# BeautifulRobot.net
KiCad netlist of a schematic drawn in EAGLE
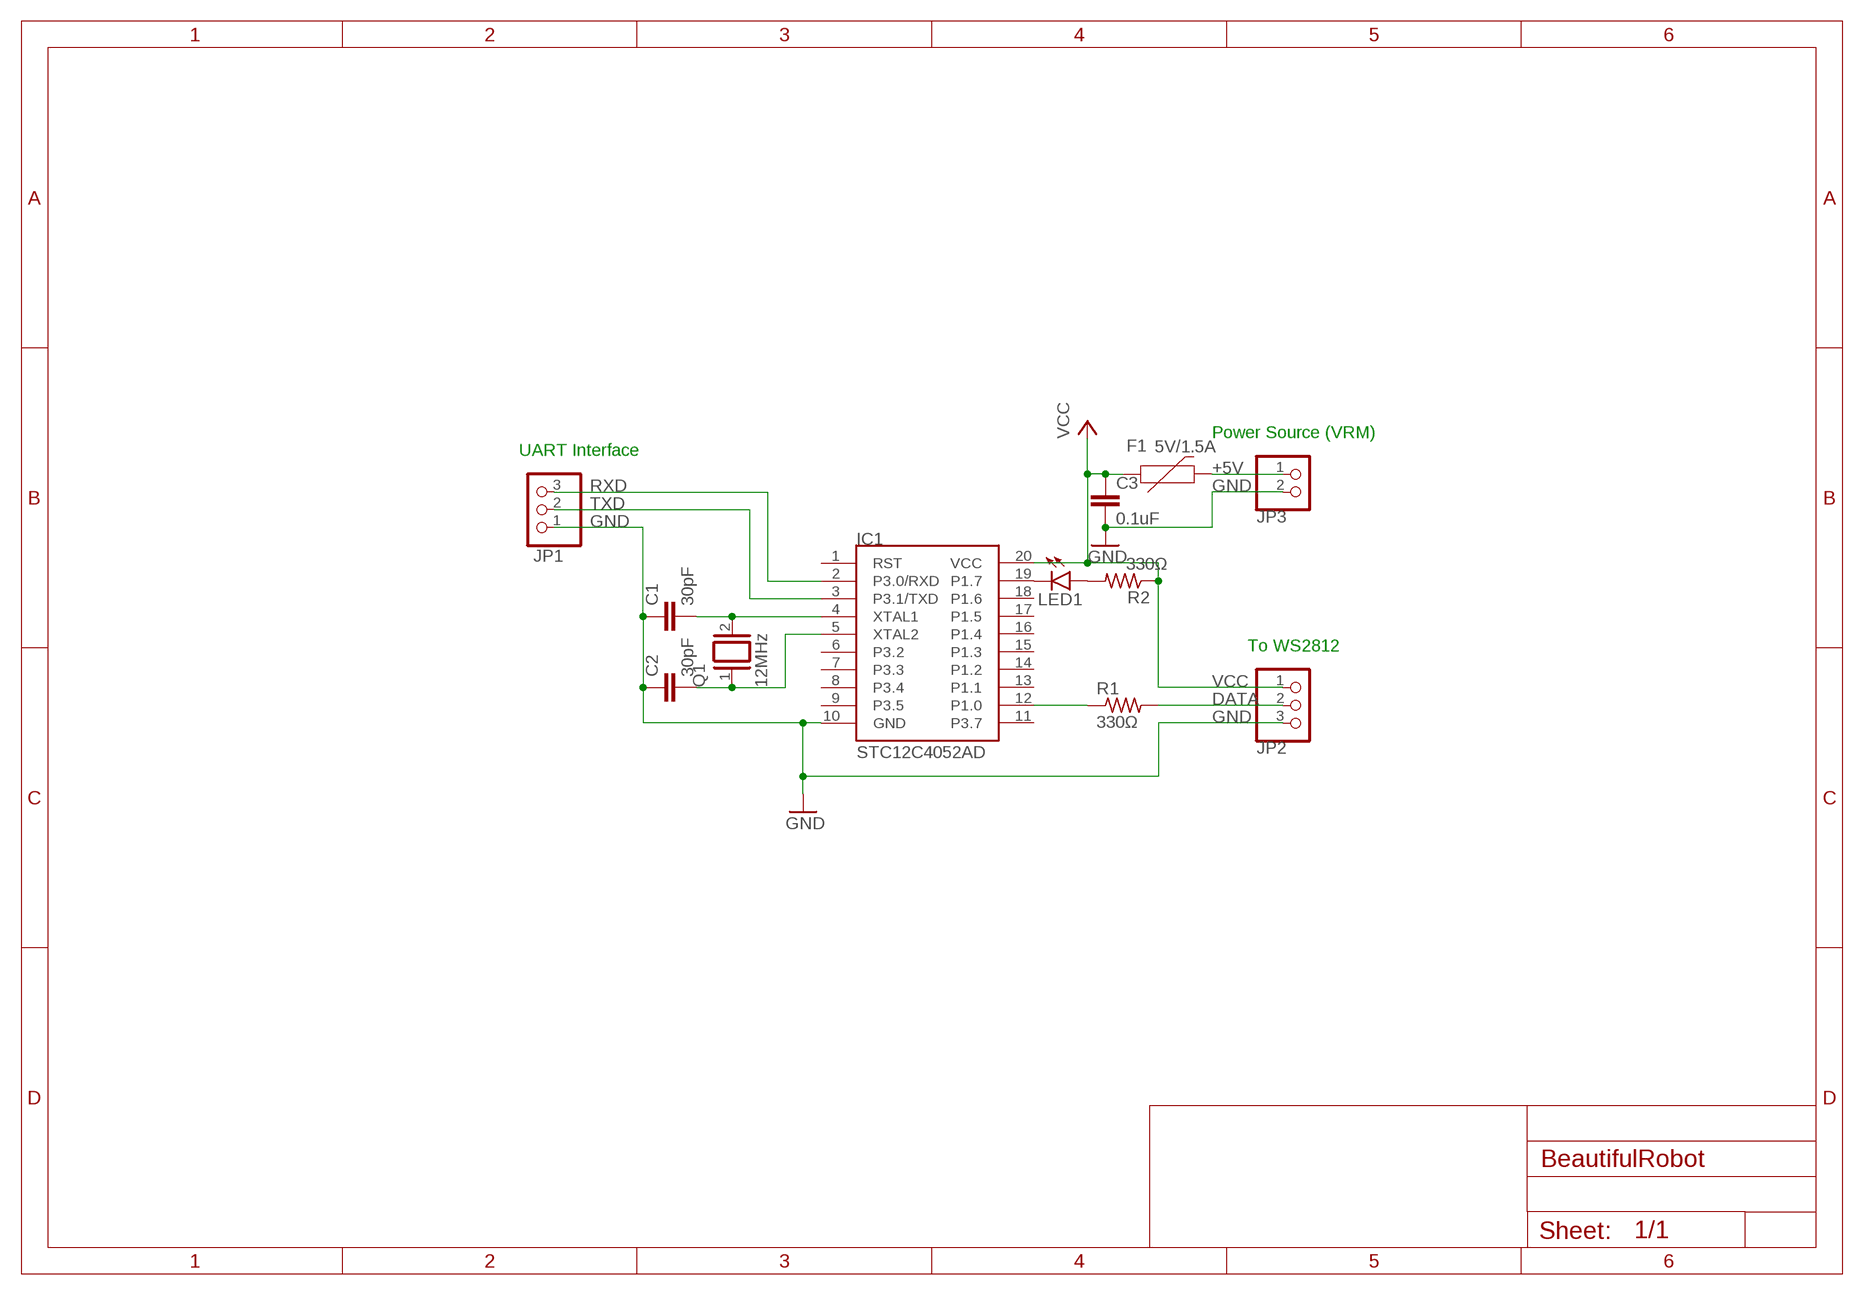
[diagram p0: schematic, sheet 1]

(export (version "E")
  (design (tool "Eeschema 10.0.6"))
  (components
    (comp (ref "C1")
      (value "30pF")
      (footprint "eagle-import:C025-025X050")
      (libsource (lib "eagle-import") (part "C-EU025-025X050"))
    )
    (comp (ref "C2")
      (value "30pF")
      (footprint "eagle-import:C025-025X050")
      (libsource (lib "eagle-import") (part "C-EU025-025X050"))
    )
    (comp (ref "C3")
      (value "0.1uF")
      (footprint "eagle-import:C025-025X050")
      (libsource (lib "eagle-import") (part "C-EU025-025X050"))
    )
    (comp (ref "F1")
      (value "5V/1.5A")
      (footprint "eagle-import:PTH")
      (libsource (lib "eagle-import") (part "PPTC_PTH"))
    )
    (comp (ref "IC1")
      (value "STC12C4052AD")
      (footprint "eagle-import:DIP762W40P254L2606H508Q20B")
      (libsource (lib "eagle-import") (part "STC12C4052AD"))
    )
    (comp (ref "JP1")
      (value "PINHD-1X3")
      (footprint "eagle-import:1X03")
      (libsource (lib "eagle-import") (part "PINHD-1X3"))
    )
    (comp (ref "JP2")
      (value "PINHD-1X3")
      (footprint "eagle-import:1X03")
      (libsource (lib "eagle-import") (part "PINHD-1X3"))
    )
    (comp (ref "JP3")
      (value "PINHD-1X2")
      (footprint "eagle-import:1X02")
      (libsource (lib "eagle-import") (part "PINHD-1X2"))
    )
    (comp (ref "LED1")
      (value "LED5MM")
      (footprint "eagle-import:LED5MM")
      (libsource (lib "eagle-import") (part "LED5MM"))
    )
    (comp (ref "Q1")
      (value "12MHz")
      (footprint "eagle-import:QS")
      (libsource (lib "eagle-import") (part "XTAL/S"))
    )
    (comp (ref "R1")
      (value "330Ω")
      (footprint "eagle-import:0204_7")
      (libsource (lib "eagle-import") (part "R-US_0204/7"))
    )
    (comp (ref "R2")
      (value "330Ω")
      (footprint "eagle-import:0204_7")
      (libsource (lib "eagle-import") (part "R-US_0204/7"))
    )
  )
  (nets
    (net (code "1") (name "/+5V") (class "Default")
      (node (ref "F1") (pin "P$2") (pinfunction "2_P$2") (pintype "bidirectional"))
      (node (ref "JP3") (pin "1") (pinfunction "1_1") (pintype "passive"))
    )
    (net (code "2") (name "/DATA") (class "Default")
      (node (ref "JP2") (pin "2") (pinfunction "2_2") (pintype "passive"))
      (node (ref "R1") (pin "2") (pinfunction "2_2") (pintype "passive"))
    )
    (net (code "3") (name "/RXD") (class "Default")
      (node (ref "IC1") (pin "2") (pinfunction "P3.0/RXD_2") (pintype "bidirectional"))
      (node (ref "JP1") (pin "3") (pinfunction "3_3") (pintype "passive"))
    )
    (net (code "4") (name "/TXD") (class "Default")
      (node (ref "IC1") (pin "3") (pinfunction "P3.1/TXD_3") (pintype "bidirectional"))
      (node (ref "JP1") (pin "2") (pinfunction "2_2") (pintype "passive"))
    )
    (net (code "5") (name "GND") (class "Default")
      (node (ref "C1") (pin "1") (pinfunction "1_1") (pintype "passive"))
      (node (ref "C2") (pin "1") (pinfunction "1_1") (pintype "passive"))
      (node (ref "C3") (pin "2") (pinfunction "2_2") (pintype "passive"))
      (node (ref "IC1") (pin "10") (pinfunction "GND_10") (pintype "power_in"))
      (node (ref "JP1") (pin "1") (pinfunction "1_1") (pintype "passive"))
      (node (ref "JP2") (pin "3") (pinfunction "3_3") (pintype "passive"))
      (node (ref "JP3") (pin "2") (pinfunction "2_2") (pintype "passive"))
    )
    (net (code "6") (name "Net-(IC1-P1.0)") (class "Default")
      (node (ref "IC1") (pin "12") (pinfunction "P1.0_12") (pintype "bidirectional"))
      (node (ref "R1") (pin "1") (pinfunction "1_1") (pintype "passive"))
    )
    (net (code "7") (name "Net-(IC1-P1.7)") (class "Default")
      (node (ref "IC1") (pin "19") (pinfunction "P1.7_19") (pintype "bidirectional"))
      (node (ref "LED1") (pin "K") (pinfunction "C_K") (pintype "passive"))
    )
    (net (code "8") (name "Net-(IC1-XTAL1)") (class "Default")
      (node (ref "C1") (pin "2") (pinfunction "2_2") (pintype "passive"))
      (node (ref "IC1") (pin "4") (pinfunction "XTAL1_4") (pintype "bidirectional"))
      (node (ref "Q1") (pin "2") (pinfunction "2_2") (pintype "passive"))
    )
    (net (code "9") (name "Net-(IC1-XTAL2)") (class "Default")
      (node (ref "C2") (pin "2") (pinfunction "2_2") (pintype "passive"))
      (node (ref "IC1") (pin "5") (pinfunction "XTAL2_5") (pintype "bidirectional"))
      (node (ref "Q1") (pin "1") (pinfunction "1_1") (pintype "passive"))
    )
    (net (code "10") (name "Net-(LED1-PadA)") (class "Default")
      (node (ref "LED1") (pin "A") (pinfunction "A_A") (pintype "passive"))
      (node (ref "R2") (pin "2") (pinfunction "2_2") (pintype "passive"))
    )
    (net (code "11") (name "VCC") (class "Default")
      (node (ref "C3") (pin "1") (pinfunction "1_1") (pintype "passive"))
      (node (ref "F1") (pin "P$1") (pinfunction "1_P$1") (pintype "bidirectional"))
      (node (ref "IC1") (pin "20") (pinfunction "VCC_20") (pintype "power_in"))
      (node (ref "JP2") (pin "1") (pinfunction "1_1") (pintype "passive"))
      (node (ref "R2") (pin "1") (pinfunction "1_1") (pintype "passive"))
    )
    (net (code "12") (name "unconnected-(IC1-P1.1-Pad13)") (class "Default")
      (node (ref "IC1") (pin "13") (pinfunction "P1.1_13") (pintype "bidirectional"))
    )
    (net (code "13") (name "unconnected-(IC1-P1.2-Pad14)") (class "Default")
      (node (ref "IC1") (pin "14") (pinfunction "P1.2_14") (pintype "bidirectional"))
    )
    (net (code "14") (name "unconnected-(IC1-P1.3-Pad15)") (class "Default")
      (node (ref "IC1") (pin "15") (pinfunction "P1.3_15") (pintype "bidirectional"))
    )
    (net (code "15") (name "unconnected-(IC1-P1.4-Pad16)") (class "Default")
      (node (ref "IC1") (pin "16") (pinfunction "P1.4_16") (pintype "bidirectional"))
    )
    (net (code "16") (name "unconnected-(IC1-P1.5-Pad17)") (class "Default")
      (node (ref "IC1") (pin "17") (pinfunction "P1.5_17") (pintype "bidirectional"))
    )
    (net (code "17") (name "unconnected-(IC1-P1.6-Pad18)") (class "Default")
      (node (ref "IC1") (pin "18") (pinfunction "P1.6_18") (pintype "bidirectional"))
    )
    (net (code "18") (name "unconnected-(IC1-P3.2-Pad6)") (class "Default")
      (node (ref "IC1") (pin "6") (pinfunction "P3.2_6") (pintype "bidirectional"))
    )
    (net (code "19") (name "unconnected-(IC1-P3.3-Pad7)") (class "Default")
      (node (ref "IC1") (pin "7") (pinfunction "P3.3_7") (pintype "bidirectional"))
    )
    (net (code "20") (name "unconnected-(IC1-P3.4-Pad8)") (class "Default")
      (node (ref "IC1") (pin "8") (pinfunction "P3.4_8") (pintype "bidirectional"))
    )
    (net (code "21") (name "unconnected-(IC1-P3.5-Pad9)") (class "Default")
      (node (ref "IC1") (pin "9") (pinfunction "P3.5_9") (pintype "bidirectional"))
    )
    (net (code "22") (name "unconnected-(IC1-P3.7-Pad11)") (class "Default")
      (node (ref "IC1") (pin "11") (pinfunction "P3.7_11") (pintype "bidirectional"))
    )
    (net (code "23") (name "unconnected-(IC1-RST-Pad1)") (class "Default")
      (node (ref "IC1") (pin "1") (pinfunction "RST_1") (pintype "bidirectional"))
    )
  )
)
